# cpc_exp_breakout.net
KiCad netlist of a schematic drawn in EAGLE
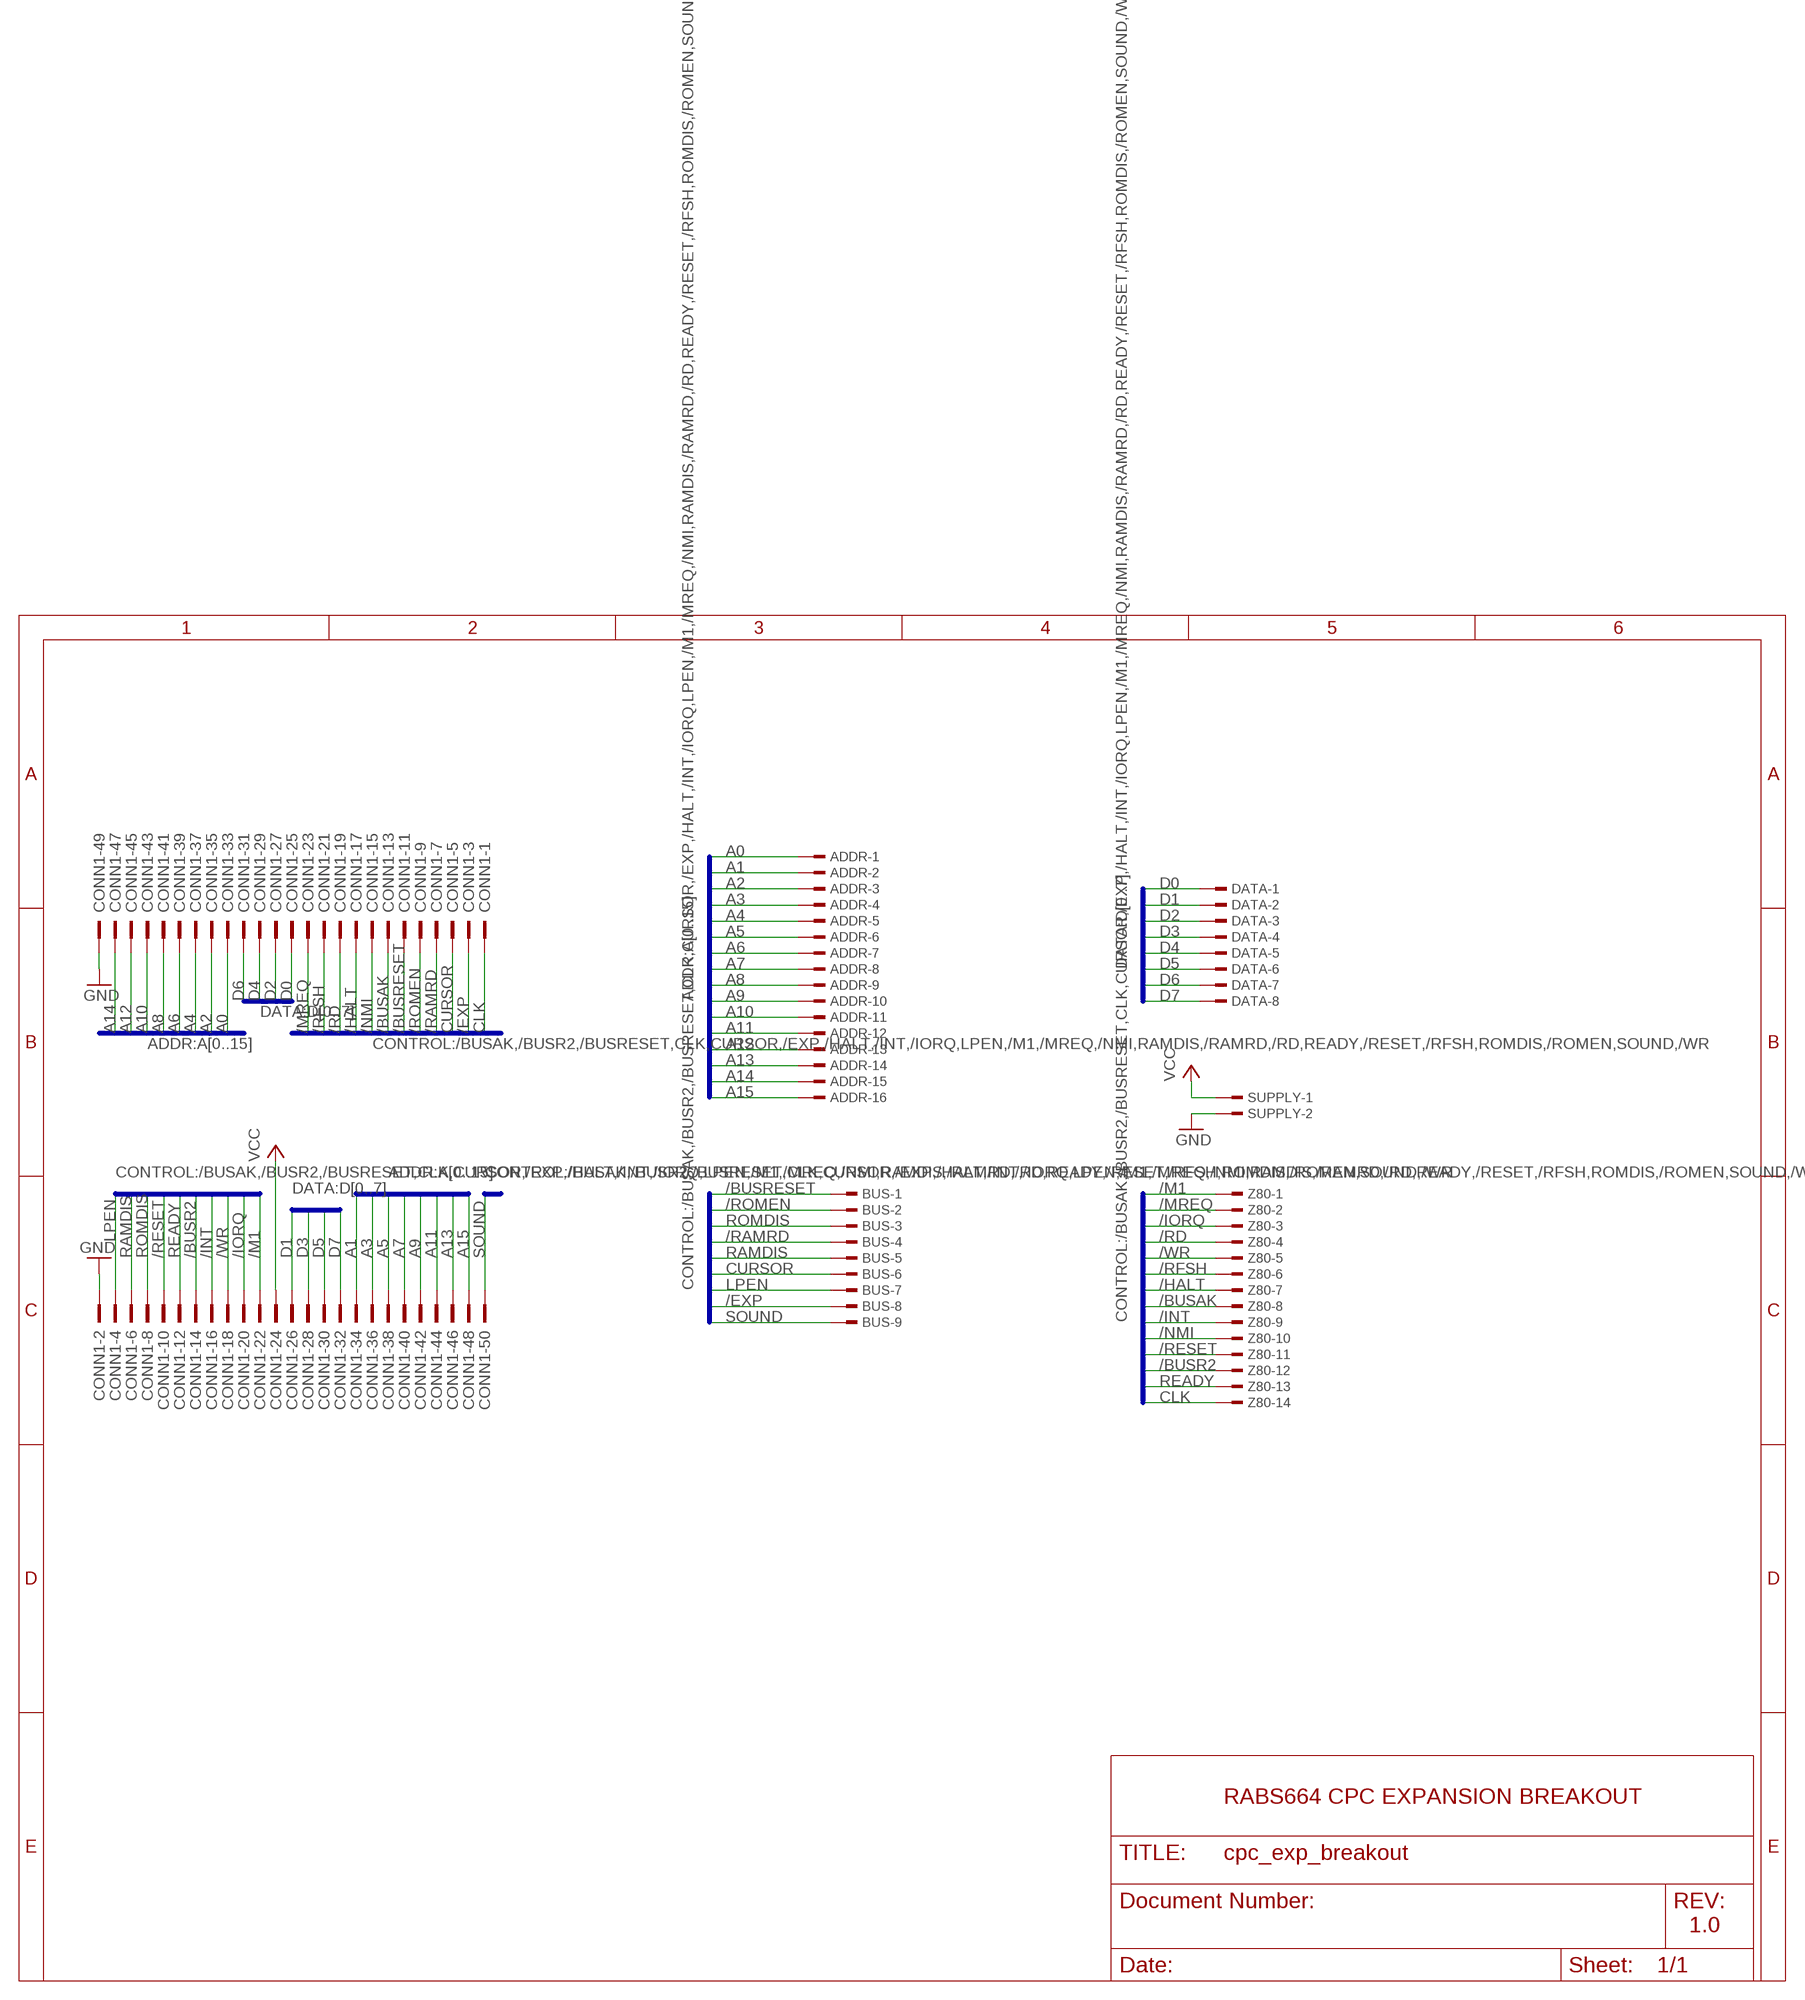
[diagram p0: schematic, sheet 1]

(export (version "E")
  (design (tool "Eeschema 10.0.6"))
  (components
    (comp (ref "ADDR")
      (value "TSW-116-07-G-S")
      (footprint "eagle-import:TSW-116-XX-G-S")
      (fields (field (name "MF") "Samtec Inc."))
      (libsource (lib "eagle-import") (part "TSW-116--G-S07"))
    )
    (comp (ref "BUS")
      (value "TSW-109-07-G-S")
      (footprint "eagle-import:TSW-109-XX-G-S")
      (fields (field (name "MF") "Samtec Inc."))
      (libsource (lib "eagle-import") (part "TSW-109--G-S07"))
    )
    (comp (ref "CONN1")
      (value "2550-")
      (footprint "eagle-import:PAK100_2500-50")
      (fields (field (name "SPICEPREFIX") "X"))
      (libsource (lib "eagle-import") (part "2550-"))
    )
    (comp (ref "DATA")
      (value "TSW-108-07-G-S")
      (footprint "eagle-import:TSW-108-XX-G-S")
      (fields (field (name "MF") "Samtec Inc."))
      (libsource (lib "eagle-import") (part "TSW-108--G-S07"))
    )
    (comp (ref "SUPPLY")
      (value "TSW-102-07-G-S")
      (footprint "eagle-import:TSW-102-XX-G-S")
      (fields (field (name "MF") "Samtec Inc."))
      (libsource (lib "eagle-import") (part "TSW-102--G-S07"))
    )
    (comp (ref "Z80")
      (value "TSW-114-07-G-S")
      (footprint "eagle-import:TSW-114-XX-G-S")
      (fields (field (name "MF") "Samtec Inc."))
      (libsource (lib "eagle-import") (part "TSW-114--G-S07"))
    )
  )
  (nets
    (net (code "26") (name "/A0") (class "Default")
      (node (ref "ADDR") (pin "1") (pinfunction "1_1") (pintype "passive"))
      (node (ref "CONN1") (pin "33") (pinfunction "KL_33") (pintype "passive"))
    )
    (net (code "27") (name "/A1") (class "Default")
      (node (ref "ADDR") (pin "2") (pinfunction "1_2") (pintype "passive"))
      (node (ref "CONN1") (pin "34") (pinfunction "KL_34") (pintype "passive"))
    )
    (net (code "28") (name "/A2") (class "Default")
      (node (ref "ADDR") (pin "3") (pinfunction "1_3") (pintype "passive"))
      (node (ref "CONN1") (pin "35") (pinfunction "KL_35") (pintype "passive"))
    )
    (net (code "29") (name "/A3") (class "Default")
      (node (ref "ADDR") (pin "4") (pinfunction "1_4") (pintype "passive"))
      (node (ref "CONN1") (pin "36") (pinfunction "KL_36") (pintype "passive"))
    )
    (net (code "30") (name "/A4") (class "Default")
      (node (ref "ADDR") (pin "5") (pinfunction "1_5") (pintype "passive"))
      (node (ref "CONN1") (pin "37") (pinfunction "KL_37") (pintype "passive"))
    )
    (net (code "31") (name "/A5") (class "Default")
      (node (ref "ADDR") (pin "6") (pinfunction "1_6") (pintype "passive"))
      (node (ref "CONN1") (pin "38") (pinfunction "KL_38") (pintype "passive"))
    )
    (net (code "32") (name "/A6") (class "Default")
      (node (ref "ADDR") (pin "7") (pinfunction "1_7") (pintype "passive"))
      (node (ref "CONN1") (pin "39") (pinfunction "KL_39") (pintype "passive"))
    )
    (net (code "33") (name "/A7") (class "Default")
      (node (ref "ADDR") (pin "8") (pinfunction "1_8") (pintype "passive"))
      (node (ref "CONN1") (pin "40") (pinfunction "KL_40") (pintype "passive"))
    )
    (net (code "34") (name "/A8") (class "Default")
      (node (ref "ADDR") (pin "9") (pinfunction "1_9") (pintype "passive"))
      (node (ref "CONN1") (pin "41") (pinfunction "KL_41") (pintype "passive"))
    )
    (net (code "35") (name "/A9") (class "Default")
      (node (ref "ADDR") (pin "10") (pinfunction "1_10") (pintype "passive"))
      (node (ref "CONN1") (pin "42") (pinfunction "KL_42") (pintype "passive"))
    )
    (net (code "36") (name "/A10") (class "Default")
      (node (ref "ADDR") (pin "11") (pinfunction "1_11") (pintype "passive"))
      (node (ref "CONN1") (pin "43") (pinfunction "KL_43") (pintype "passive"))
    )
    (net (code "37") (name "/A11") (class "Default")
      (node (ref "ADDR") (pin "12") (pinfunction "1_12") (pintype "passive"))
      (node (ref "CONN1") (pin "44") (pinfunction "KL_44") (pintype "passive"))
    )
    (net (code "38") (name "/A12") (class "Default")
      (node (ref "ADDR") (pin "13") (pinfunction "1_13") (pintype "passive"))
      (node (ref "CONN1") (pin "45") (pinfunction "KL_45") (pintype "passive"))
    )
    (net (code "39") (name "/A13") (class "Default")
      (node (ref "ADDR") (pin "14") (pinfunction "1_14") (pintype "passive"))
      (node (ref "CONN1") (pin "46") (pinfunction "KL_46") (pintype "passive"))
    )
    (net (code "40") (name "/A14") (class "Default")
      (node (ref "ADDR") (pin "15") (pinfunction "1_15") (pintype "passive"))
      (node (ref "CONN1") (pin "47") (pinfunction "KL_47") (pintype "passive"))
    )
    (net (code "41") (name "/A15") (class "Default")
      (node (ref "ADDR") (pin "16") (pinfunction "1_16") (pintype "passive"))
      (node (ref "CONN1") (pin "48") (pinfunction "KL_48") (pintype "passive"))
    )
    (net (code "43") (name "/CLK") (class "Default")
      (node (ref "CONN1") (pin "1") (pinfunction "KL_1") (pintype "passive"))
      (node (ref "Z80") (pin "14") (pinfunction "1_14") (pintype "passive"))
    )
    (net (code "44") (name "/CURSOR") (class "Default")
      (node (ref "BUS") (pin "6") (pinfunction "1_6") (pintype "passive"))
      (node (ref "CONN1") (pin "5") (pinfunction "KL_5") (pintype "passive"))
    )
    (net (code "45") (name "/D0") (class "Default")
      (node (ref "CONN1") (pin "25") (pinfunction "KL_25") (pintype "passive"))
      (node (ref "DATA") (pin "1") (pinfunction "1_1") (pintype "passive"))
    )
    (net (code "46") (name "/D1") (class "Default")
      (node (ref "CONN1") (pin "26") (pinfunction "KL_26") (pintype "passive"))
      (node (ref "DATA") (pin "2") (pinfunction "1_2") (pintype "passive"))
    )
    (net (code "47") (name "/D2") (class "Default")
      (node (ref "CONN1") (pin "27") (pinfunction "KL_27") (pintype "passive"))
      (node (ref "DATA") (pin "3") (pinfunction "1_3") (pintype "passive"))
    )
    (net (code "48") (name "/D3") (class "Default")
      (node (ref "CONN1") (pin "28") (pinfunction "KL_28") (pintype "passive"))
      (node (ref "DATA") (pin "4") (pinfunction "1_4") (pintype "passive"))
    )
    (net (code "49") (name "/D4") (class "Default")
      (node (ref "CONN1") (pin "29") (pinfunction "KL_29") (pintype "passive"))
      (node (ref "DATA") (pin "5") (pinfunction "1_5") (pintype "passive"))
    )
    (net (code "50") (name "/D5") (class "Default")
      (node (ref "CONN1") (pin "30") (pinfunction "KL_30") (pintype "passive"))
      (node (ref "DATA") (pin "6") (pinfunction "1_6") (pintype "passive"))
    )
    (net (code "51") (name "/D6") (class "Default")
      (node (ref "CONN1") (pin "31") (pinfunction "KL_31") (pintype "passive"))
      (node (ref "DATA") (pin "7") (pinfunction "1_7") (pintype "passive"))
    )
    (net (code "52") (name "/D7") (class "Default")
      (node (ref "CONN1") (pin "32") (pinfunction "KL_32") (pintype "passive"))
      (node (ref "DATA") (pin "8") (pinfunction "1_8") (pintype "passive"))
    )
    (net (code "54") (name "/LPEN") (class "Default")
      (node (ref "BUS") (pin "7") (pinfunction "1_7") (pintype "passive"))
      (node (ref "CONN1") (pin "4") (pinfunction "KL_4") (pintype "passive"))
    )
    (net (code "55") (name "/RAMDIS") (class "Default")
      (node (ref "BUS") (pin "5") (pinfunction "1_5") (pintype "passive"))
      (node (ref "CONN1") (pin "6") (pinfunction "KL_6") (pintype "passive"))
    )
    (net (code "56") (name "/READY") (class "Default")
      (node (ref "CONN1") (pin "12") (pinfunction "KL_12") (pintype "passive"))
      (node (ref "Z80") (pin "13") (pinfunction "1_13") (pintype "passive"))
    )
    (net (code "57") (name "/ROMDIS") (class "Default")
      (node (ref "BUS") (pin "3") (pinfunction "1_3") (pintype "passive"))
      (node (ref "CONN1") (pin "8") (pinfunction "KL_8") (pintype "passive"))
    )
    (net (code "58") (name "/SOUND") (class "Default")
      (node (ref "BUS") (pin "9") (pinfunction "1_9") (pintype "passive"))
      (node (ref "CONN1") (pin "50") (pinfunction "KL_50") (pintype "passive"))
    )
    (net (code "60") (name "/{slash}BUSAK") (class "Default")
      (node (ref "CONN1") (pin "13") (pinfunction "KL_13") (pintype "passive"))
      (node (ref "Z80") (pin "8") (pinfunction "1_8") (pintype "passive"))
    )
    (net (code "61") (name "/{slash}BUSR2") (class "Default")
      (node (ref "CONN1") (pin "14") (pinfunction "KL_14") (pintype "passive"))
      (node (ref "Z80") (pin "12") (pinfunction "1_12") (pintype "passive"))
    )
    (net (code "62") (name "/{slash}BUSRESET") (class "Default")
      (node (ref "BUS") (pin "1") (pinfunction "1_1") (pintype "passive"))
      (node (ref "CONN1") (pin "11") (pinfunction "KL_11") (pintype "passive"))
    )
    (net (code "63") (name "/{slash}EXP") (class "Default")
      (node (ref "BUS") (pin "8") (pinfunction "1_8") (pintype "passive"))
      (node (ref "CONN1") (pin "3") (pinfunction "KL_3") (pintype "passive"))
    )
    (net (code "64") (name "/{slash}HALT") (class "Default")
      (node (ref "CONN1") (pin "17") (pinfunction "KL_17") (pintype "passive"))
      (node (ref "Z80") (pin "7") (pinfunction "1_7") (pintype "passive"))
    )
    (net (code "65") (name "/{slash}INT") (class "Default")
      (node (ref "CONN1") (pin "16") (pinfunction "KL_16") (pintype "passive"))
      (node (ref "Z80") (pin "9") (pinfunction "1_9") (pintype "passive"))
    )
    (net (code "66") (name "/{slash}IORQ") (class "Default")
      (node (ref "CONN1") (pin "20") (pinfunction "KL_20") (pintype "passive"))
      (node (ref "Z80") (pin "3") (pinfunction "1_3") (pintype "passive"))
    )
    (net (code "67") (name "/{slash}M1") (class "Default")
      (node (ref "CONN1") (pin "22") (pinfunction "KL_22") (pintype "passive"))
      (node (ref "Z80") (pin "1") (pinfunction "1_1") (pintype "passive"))
    )
    (net (code "68") (name "/{slash}MREQ") (class "Default")
      (node (ref "CONN1") (pin "23") (pinfunction "KL_23") (pintype "passive"))
      (node (ref "Z80") (pin "2") (pinfunction "1_2") (pintype "passive"))
    )
    (net (code "69") (name "/{slash}NMI") (class "Default")
      (node (ref "CONN1") (pin "15") (pinfunction "KL_15") (pintype "passive"))
      (node (ref "Z80") (pin "10") (pinfunction "1_10") (pintype "passive"))
    )
    (net (code "70") (name "/{slash}RAMRD") (class "Default")
      (node (ref "BUS") (pin "4") (pinfunction "1_4") (pintype "passive"))
      (node (ref "CONN1") (pin "7") (pinfunction "KL_7") (pintype "passive"))
    )
    (net (code "71") (name "/{slash}RD") (class "Default")
      (node (ref "CONN1") (pin "19") (pinfunction "KL_19") (pintype "passive"))
      (node (ref "Z80") (pin "4") (pinfunction "1_4") (pintype "passive"))
    )
    (net (code "72") (name "/{slash}RESET") (class "Default")
      (node (ref "CONN1") (pin "10") (pinfunction "KL_10") (pintype "passive"))
      (node (ref "Z80") (pin "11") (pinfunction "1_11") (pintype "passive"))
    )
    (net (code "73") (name "/{slash}RFSH") (class "Default")
      (node (ref "CONN1") (pin "21") (pinfunction "KL_21") (pintype "passive"))
      (node (ref "Z80") (pin "6") (pinfunction "1_6") (pintype "passive"))
    )
    (net (code "74") (name "/{slash}ROMEN") (class "Default")
      (node (ref "BUS") (pin "2") (pinfunction "1_2") (pintype "passive"))
      (node (ref "CONN1") (pin "9") (pinfunction "KL_9") (pintype "passive"))
    )
    (net (code "75") (name "/{slash}WR") (class "Default")
      (node (ref "CONN1") (pin "18") (pinfunction "KL_18") (pintype "passive"))
      (node (ref "Z80") (pin "5") (pinfunction "1_5") (pintype "passive"))
    )
    (net (code "76") (name "GND") (class "Default")
      (node (ref "CONN1") (pin "2") (pinfunction "KL_2") (pintype "passive"))
      (node (ref "CONN1") (pin "49") (pinfunction "KL_49") (pintype "passive"))
      (node (ref "SUPPLY") (pin "2") (pinfunction "1_2") (pintype "passive"))
    )
    (net (code "77") (name "VCC") (class "Default")
      (node (ref "CONN1") (pin "24") (pinfunction "KL_24") (pintype "passive"))
      (node (ref "SUPPLY") (pin "1") (pinfunction "1_1") (pintype "passive"))
    )
  )
)
